# Esquem_tico.net
KiCad netlist of a schematic drawn in EAGLE
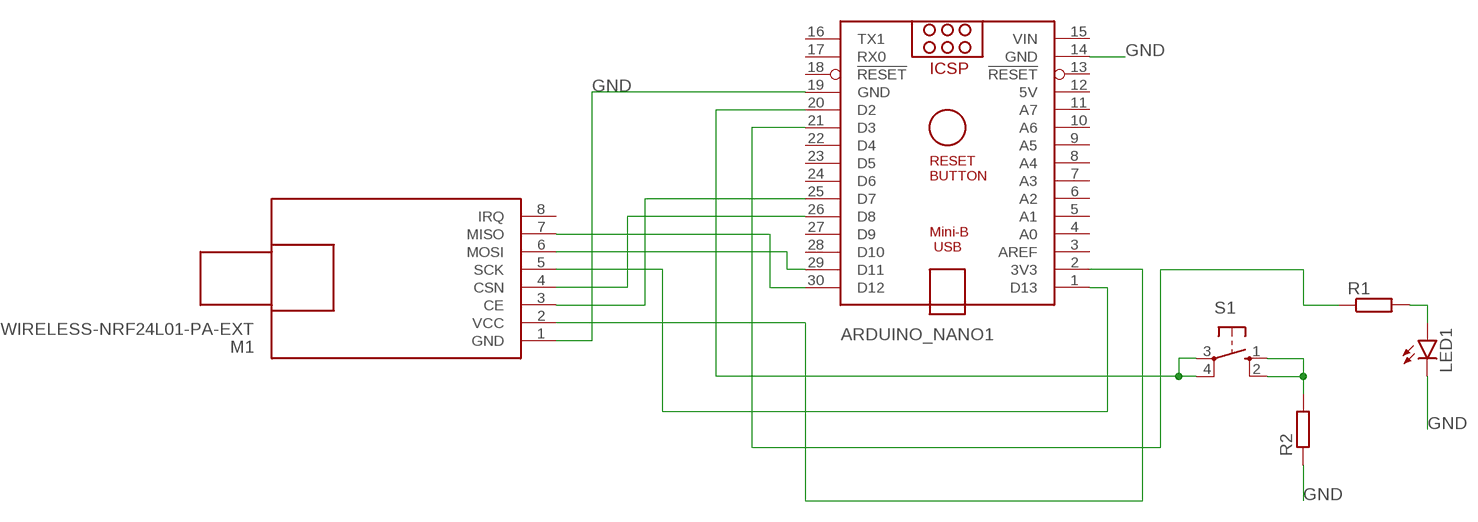
[diagram p0: schematic, sheet 1]

(export (version "E")
  (design (tool "Eeschema 10.0.6"))
  (components
    (comp (ref "ARDUINO_NANO1")
      (value "ARDUINO_NANO")
      (footprint "eagle-import:ARDUINO_NANO")
      (libsource (lib "eagle-import") (part "ARDUINO_NANO"))
    )
    (comp (ref "LED1")
      (value "LED5MM")
      (footprint "eagle-import:LED5MM")
      (libsource (lib "eagle-import") (part "LED5MM"))
    )
    (comp (ref "M1")
      (value "WIRELESS-NRF24L01-PA-EXT")
      (footprint "eagle-import:WIRELESS-NRF24L01-PA-EXT")
      (libsource (lib "eagle-import") (part "WIRELESS-NRF24L01-PA-EXT"))
    )
    (comp (ref "R1")
      (value "R-EU_0207/10")
      (footprint "eagle-import:0207_10")
      (libsource (lib "eagle-import") (part "R-EU_0207/10"))
    )
    (comp (ref "R2")
      (value "R-EU_0207/10")
      (footprint "eagle-import:0207_10")
      (libsource (lib "eagle-import") (part "R-EU_0207/10"))
    )
    (comp (ref "S1")
      (value "10-XX")
      (footprint "eagle-import:B3F-10XX")
      (fields (field (name "MPN") "B3F-1000"))
      (libsource (lib "eagle-import") (part "10-XX"))
    )
  )
  (nets
    (net (code "1") (name "/5V") (class "Default")
      (node (ref "ARDUINO_NANO1") (pin "12") (pinfunction "5V_12") (pintype "power_in"))
    )
    (net (code "2") (name "/GND") (class "Default")
      (node (ref "ARDUINO_NANO1") (pin "14") (pinfunction "GND_14") (pintype "power_in"))
      (node (ref "ARDUINO_NANO1") (pin "19") (pinfunction "GND_19") (pintype "power_in"))
      (node (ref "LED1") (pin "K") (pinfunction "C_K") (pintype "passive"))
      (node (ref "M1") (pin "1") (pinfunction "GND_1") (pintype "power_in"))
      (node (ref "R2") (pin "1") (pinfunction "1_1") (pintype "passive"))
    )
    (net (code "3") (name "/VIN") (class "Default")
      (node (ref "ARDUINO_NANO1") (pin "15") (pinfunction "VIN_15") (pintype "power_in"))
    )
    (net (code "4") (name "Net-(ARDUINO_NANO1-3V3)") (class "Default")
      (node (ref "ARDUINO_NANO1") (pin "2") (pinfunction "3V3_2") (pintype "output"))
      (node (ref "M1") (pin "2") (pinfunction "VCC_2") (pintype "power_in"))
    )
    (net (code "5") (name "Net-(ARDUINO_NANO1-D2)") (class "Default")
      (node (ref "ARDUINO_NANO1") (pin "20") (pinfunction "D2_20") (pintype "bidirectional"))
      (node (ref "S1") (pin "3") (pinfunction "P_3") (pintype "passive"))
      (node (ref "S1") (pin "4") (pinfunction "P1_4") (pintype "passive"))
    )
    (net (code "6") (name "Net-(ARDUINO_NANO1-D3)") (class "Default")
      (node (ref "ARDUINO_NANO1") (pin "21") (pinfunction "D3_21") (pintype "bidirectional"))
      (node (ref "R1") (pin "1") (pinfunction "1_1") (pintype "passive"))
    )
    (net (code "7") (name "Net-(ARDUINO_NANO1-D7)") (class "Default")
      (node (ref "ARDUINO_NANO1") (pin "25") (pinfunction "D7_25") (pintype "bidirectional"))
      (node (ref "M1") (pin "3") (pinfunction "CE_3") (pintype "bidirectional"))
    )
    (net (code "8") (name "Net-(ARDUINO_NANO1-D8)") (class "Default")
      (node (ref "ARDUINO_NANO1") (pin "26") (pinfunction "D8_26") (pintype "bidirectional"))
      (node (ref "M1") (pin "4") (pinfunction "CSN_4") (pintype "bidirectional"))
    )
    (net (code "9") (name "Net-(ARDUINO_NANO1-D11)") (class "Default")
      (node (ref "ARDUINO_NANO1") (pin "29") (pinfunction "D11_29") (pintype "bidirectional"))
      (node (ref "M1") (pin "6") (pinfunction "MOSI_6") (pintype "bidirectional"))
    )
    (net (code "10") (name "Net-(ARDUINO_NANO1-D12)") (class "Default")
      (node (ref "ARDUINO_NANO1") (pin "30") (pinfunction "D12_30") (pintype "bidirectional"))
      (node (ref "M1") (pin "7") (pinfunction "MISO_7") (pintype "bidirectional"))
    )
    (net (code "11") (name "Net-(ARDUINO_NANO1-D13)") (class "Default")
      (node (ref "ARDUINO_NANO1") (pin "1") (pinfunction "D13_1") (pintype "bidirectional"))
      (node (ref "M1") (pin "5") (pinfunction "SCK_5") (pintype "bidirectional"))
    )
    (net (code "12") (name "Net-(LED1-PadA)") (class "Default")
      (node (ref "LED1") (pin "A") (pinfunction "A_A") (pintype "passive"))
      (node (ref "R1") (pin "2") (pinfunction "2_2") (pintype "passive"))
    )
    (net (code "13") (name "Net-(S1-S)") (class "Default")
      (node (ref "R2") (pin "2") (pinfunction "2_2") (pintype "passive"))
      (node (ref "S1") (pin "1") (pinfunction "S_1") (pintype "passive"))
      (node (ref "S1") (pin "2") (pinfunction "S1_2") (pintype "passive"))
    )
    (net (code "14") (name "unconnected-(ARDUINO_NANO1-A0-Pad4)") (class "Default")
      (node (ref "ARDUINO_NANO1") (pin "4") (pinfunction "A0_4") (pintype "bidirectional"))
    )
    (net (code "15") (name "unconnected-(ARDUINO_NANO1-A1-Pad5)") (class "Default")
      (node (ref "ARDUINO_NANO1") (pin "5") (pinfunction "A1_5") (pintype "bidirectional"))
    )
    (net (code "16") (name "unconnected-(ARDUINO_NANO1-A2-Pad6)") (class "Default")
      (node (ref "ARDUINO_NANO1") (pin "6") (pinfunction "A2_6") (pintype "bidirectional"))
    )
    (net (code "17") (name "unconnected-(ARDUINO_NANO1-A3-Pad7)") (class "Default")
      (node (ref "ARDUINO_NANO1") (pin "7") (pinfunction "A3_7") (pintype "bidirectional"))
    )
    (net (code "18") (name "unconnected-(ARDUINO_NANO1-A4-Pad8)") (class "Default")
      (node (ref "ARDUINO_NANO1") (pin "8") (pinfunction "A4_8") (pintype "bidirectional"))
    )
    (net (code "19") (name "unconnected-(ARDUINO_NANO1-A5-Pad9)") (class "Default")
      (node (ref "ARDUINO_NANO1") (pin "9") (pinfunction "A5_9") (pintype "bidirectional"))
    )
    (net (code "20") (name "unconnected-(ARDUINO_NANO1-A6-Pad10)") (class "Default")
      (node (ref "ARDUINO_NANO1") (pin "10") (pinfunction "A6_10") (pintype "bidirectional"))
    )
    (net (code "21") (name "unconnected-(ARDUINO_NANO1-A7-Pad11)") (class "Default")
      (node (ref "ARDUINO_NANO1") (pin "11") (pinfunction "A7_11") (pintype "bidirectional"))
    )
    (net (code "22") (name "unconnected-(ARDUINO_NANO1-AREF-Pad3)") (class "Default")
      (node (ref "ARDUINO_NANO1") (pin "3") (pinfunction "AREF_3") (pintype "input"))
    )
    (net (code "23") (name "unconnected-(ARDUINO_NANO1-D4-Pad22)") (class "Default")
      (node (ref "ARDUINO_NANO1") (pin "22") (pinfunction "D4_22") (pintype "bidirectional"))
    )
    (net (code "24") (name "unconnected-(ARDUINO_NANO1-D5-Pad23)") (class "Default")
      (node (ref "ARDUINO_NANO1") (pin "23") (pinfunction "D5_23") (pintype "bidirectional"))
    )
    (net (code "25") (name "unconnected-(ARDUINO_NANO1-D6-Pad24)") (class "Default")
      (node (ref "ARDUINO_NANO1") (pin "24") (pinfunction "D6_24") (pintype "bidirectional"))
    )
    (net (code "26") (name "unconnected-(ARDUINO_NANO1-D9-Pad27)") (class "Default")
      (node (ref "ARDUINO_NANO1") (pin "27") (pinfunction "D9_27") (pintype "bidirectional"))
    )
    (net (code "27") (name "unconnected-(ARDUINO_NANO1-D10-Pad28)") (class "Default")
      (node (ref "ARDUINO_NANO1") (pin "28") (pinfunction "D10_28") (pintype "bidirectional"))
    )
    (net (code "28") (name "unconnected-(ARDUINO_NANO1-RX0-Pad17)") (class "Default")
      (node (ref "ARDUINO_NANO1") (pin "17") (pinfunction "RX0_17") (pintype "bidirectional"))
    )
    (net (code "29") (name "unconnected-(ARDUINO_NANO1-TX1-Pad16)") (class "Default")
      (node (ref "ARDUINO_NANO1") (pin "16") (pinfunction "TX1_16") (pintype "bidirectional"))
    )
    (net (code "30") (name "unconnected-(ARDUINO_NANO1-~{RESET}-Pad13)") (class "Default")
      (node (ref "ARDUINO_NANO1") (pin "13") (pinfunction "~{RESET}_13") (pintype "input"))
    )
    (net (code "31") (name "unconnected-(ARDUINO_NANO1-~{RESET}-Pad18)") (class "Default")
      (node (ref "ARDUINO_NANO1") (pin "18") (pinfunction "~{RESET}_18") (pintype "input"))
    )
    (net (code "32") (name "unconnected-(M1-IRQ-Pad8)") (class "Default")
      (node (ref "M1") (pin "8") (pinfunction "IRQ_8") (pintype "bidirectional"))
    )
  )
)
